# IOIO-OTG.net
KiCad netlist of a schematic drawn in EAGLE
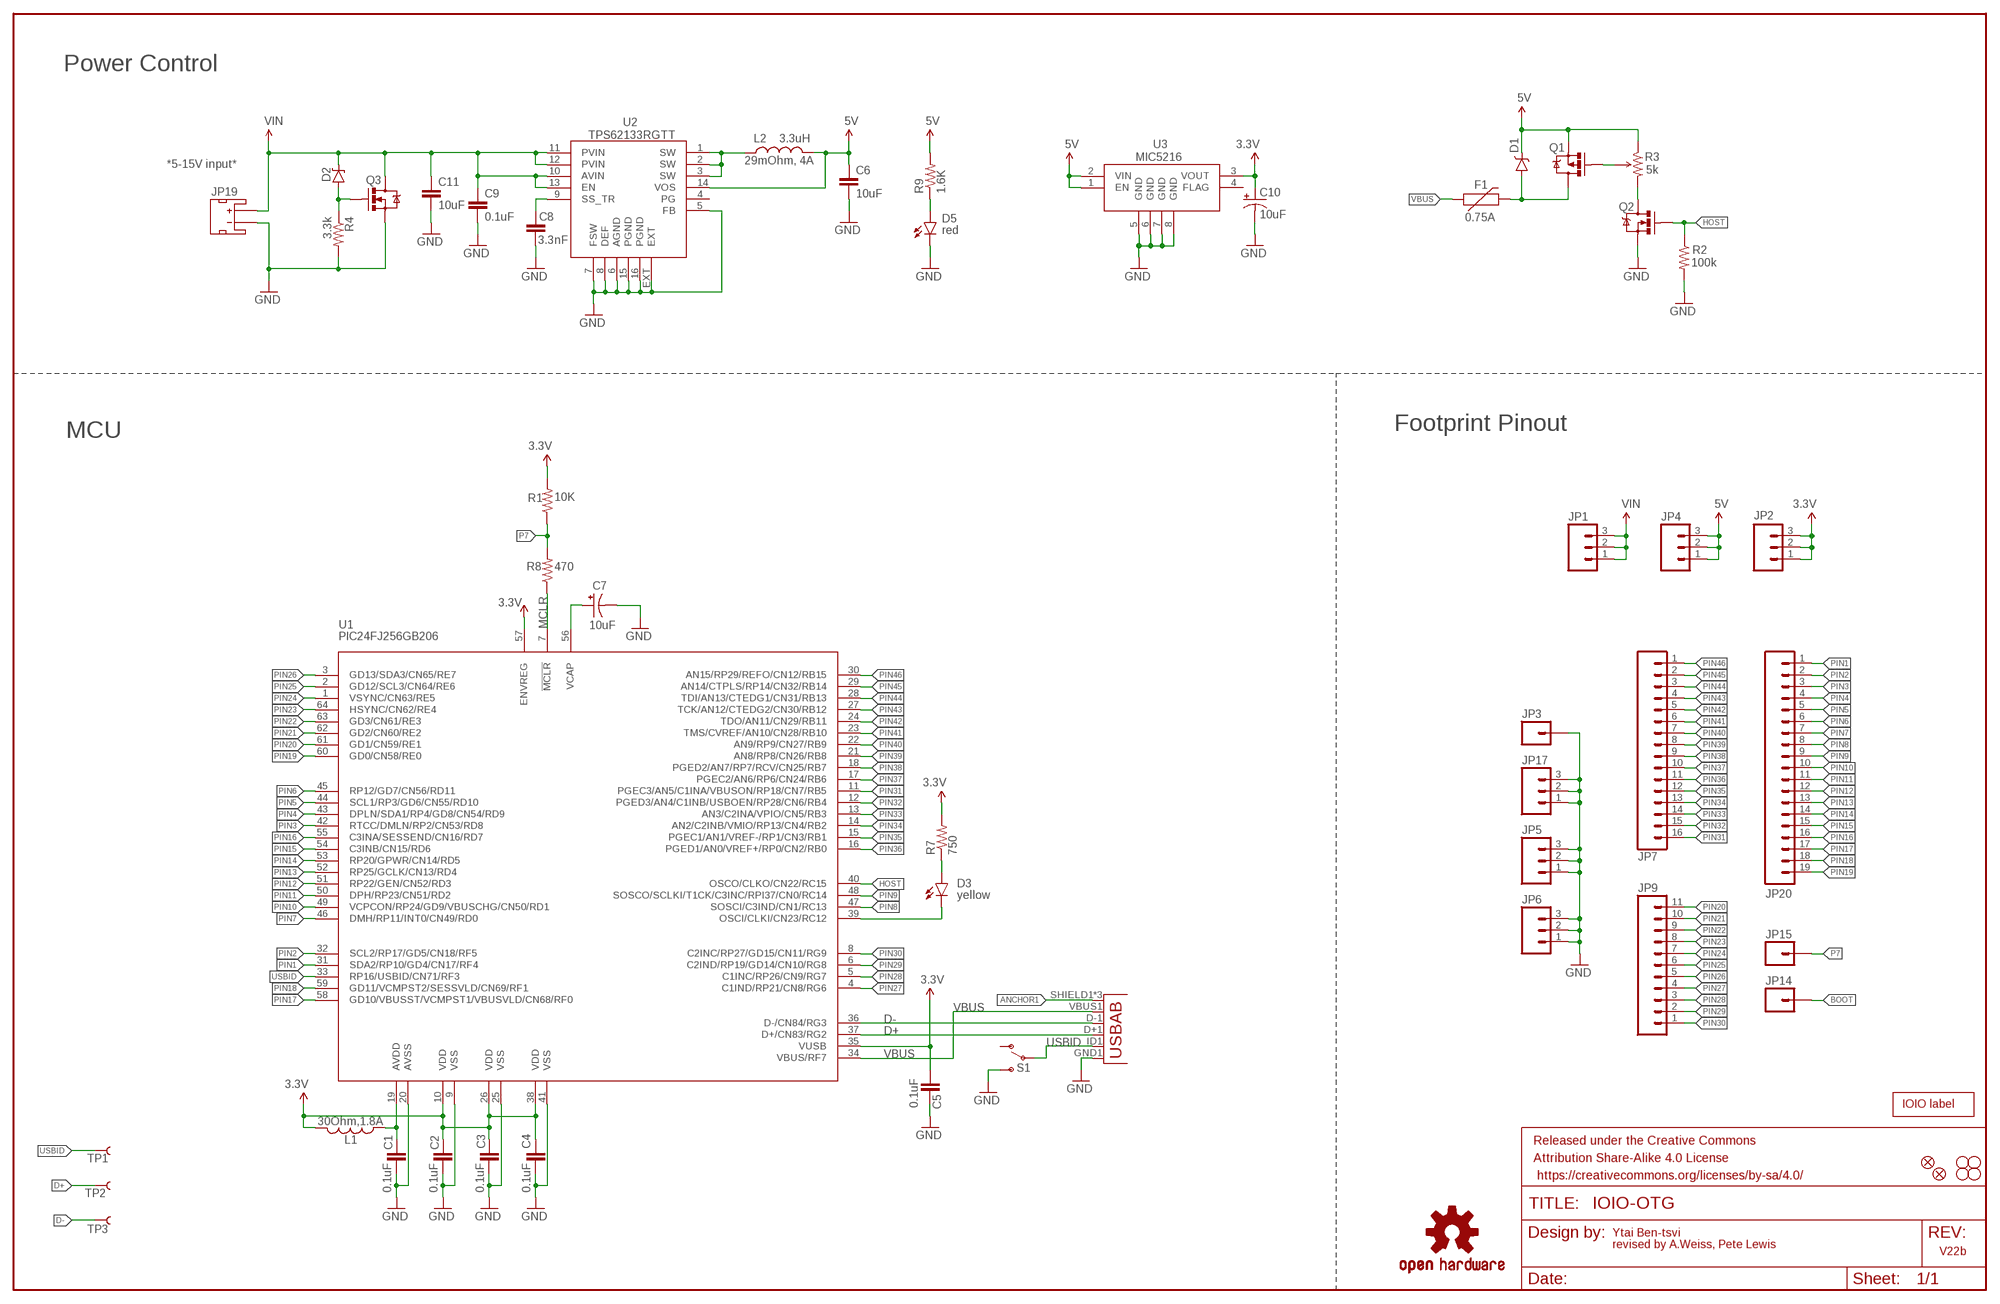
[diagram p0: schematic, sheet 1]

(export (version "E")
  (design (tool "Eeschema 10.0.6"))
  (components
    (comp (ref "C1")
      (value "0.1uF")
      (footprint "eagle-import:0603-CAP")
      (libsource (lib "eagle-import") (part "0.1UF-25V(+80/-20%)(0603)"))
    )
    (comp (ref "C2")
      (value "0.1uF")
      (footprint "eagle-import:0603-CAP")
      (libsource (lib "eagle-import") (part "0.1UF-25V(+80/-20%)(0603)"))
    )
    (comp (ref "C3")
      (value "0.1uF")
      (footprint "eagle-import:0603-CAP")
      (libsource (lib "eagle-import") (part "0.1UF-25V(+80/-20%)(0603)"))
    )
    (comp (ref "C4")
      (value "0.1uF")
      (footprint "eagle-import:0603-CAP")
      (libsource (lib "eagle-import") (part "0.1UF-25V(+80/-20%)(0603)"))
    )
    (comp (ref "C5")
      (value "0.1uF")
      (footprint "eagle-import:0603-CAP")
      (libsource (lib "eagle-import") (part "0.1UF-25V(+80/-20%)(0603)"))
    )
    (comp (ref "C6")
      (value "10uF")
      (footprint "eagle-import:0805-CAP")
      (fields (field (name "PART#") "LMK212BJ106KG-T"))
      (libsource (lib "eagle-import") (part "10UF10V10%(0805)"))
    )
    (comp (ref "C7")
      (value "10uF")
      (footprint "eagle-import:EIA3216")
      (libsource (lib "eagle-import") (part "10UF-16V-10%(TANT)"))
    )
    (comp (ref "C8")
      (value "3.3nF")
      (footprint "eagle-import:0603-CAP")
      (libsource (lib "eagle-import") (part "3.3NF-100V-10%(0603)"))
    )
    (comp (ref "C9")
      (value "0.1uF")
      (footprint "eagle-import:0603-CAP")
      (libsource (lib "eagle-import") (part "0.1UF-25V(+80/-20%)(0603)"))
    )
    (comp (ref "C10")
      (value "10uF")
      (footprint "eagle-import:EIA3216")
      (fields (field (name "PART#") "TAJA106K016RNJ"))
      (libsource (lib "eagle-import") (part "10UF-16V-10%(TANT)"))
    )
    (comp (ref "C11")
      (value "10uF")
      (footprint "eagle-import:1210")
      (fields (field (name "PART#") "UMK325C7106MM-T"))
      (libsource (lib "eagle-import") (part "10UF50V20%(1210)"))
    )
    (comp (ref "D1")
      (value "B340A")
      (footprint "eagle-import:SMA-DIODE")
      (fields (field (name "PART#") "B340A"))
      (libsource (lib "eagle-import") (part "DIODE-SCHOTTKY-B340A"))
    )
    (comp (ref "D2")
      (value "DZ2J160M0L")
      (footprint "eagle-import:PANASONIC_SMINI2-F5-B")
      (fields (field (name "PART#") "DZ2J150M0L"))
      (libsource (lib "eagle-import") (part "DIODE-ZENERDZ2J150M0L"))
    )
    (comp (ref "D3")
      (value "Yellow")
      (footprint "eagle-import:LED-0603")
      (libsource (lib "eagle-import") (part "LED-YELLOW0603-SMART"))
    )
    (comp (ref "D5")
      (value "Red")
      (footprint "eagle-import:LED-0603")
      (libsource (lib "eagle-import") (part "LED-RED0603-SMART"))
    )
    (comp (ref "F1")
      (value "0.75A")
      (footprint "eagle-import:PTC-1206")
      (fields (field (name "PART#") "0ZCA0075FF2G"))
      (libsource (lib "eagle-import") (part "PTCSMD"))
    )
    (comp (ref "FRAME2")
      (value "FRAME-LEDGER")
      (footprint "eagle-import:CREATIVE_COMMONS")
      (libsource (lib "eagle-import") (part "FRAME-LEDGER"))
    )
    (comp (ref "JP1")
      (value "M03PTH")
      (footprint "eagle-import:1X03")
      (libsource (lib "eagle-import") (part "M03PTH"))
    )
    (comp (ref "JP2")
      (value "M03PTH")
      (footprint "eagle-import:1X03")
      (libsource (lib "eagle-import") (part "M03PTH"))
    )
    (comp (ref "JP3")
      (value "M01PTH")
      (footprint "eagle-import:1X01")
      (libsource (lib "eagle-import") (part "M01PTH"))
    )
    (comp (ref "JP4")
      (value "M03PTH")
      (footprint "eagle-import:1X03")
      (libsource (lib "eagle-import") (part "M03PTH"))
    )
    (comp (ref "JP5")
      (value "M03PTH")
      (footprint "eagle-import:1X03")
      (libsource (lib "eagle-import") (part "M03PTH"))
    )
    (comp (ref "JP6")
      (value "M03PTH")
      (footprint "eagle-import:1X03")
      (libsource (lib "eagle-import") (part "M03PTH"))
    )
    (comp (ref "JP7")
      (value "M161X16_NO_SILK")
      (footprint "eagle-import:1X16_NO_SILK")
      (libsource (lib "eagle-import") (part "M161X16_NO_SILK"))
    )
    (comp (ref "JP8")
      (value "FIDUCIALUFIDUCIAL")
      (footprint "eagle-import:MICRO-FIDUCIAL")
      (libsource (lib "eagle-import") (part "FIDUCIALUFIDUCIAL"))
    )
    (comp (ref "JP9")
      (value "M111X11_NO_SILK")
      (footprint "eagle-import:1X11_NO_SILK")
      (libsource (lib "eagle-import") (part "M111X11_NO_SILK"))
    )
    (comp (ref "JP10")
      (value "STAND-OFF")
      (footprint "eagle-import:STAND-OFF")
      (libsource (lib "eagle-import") (part "STAND-OFF"))
    )
    (comp (ref "JP11")
      (value "STAND-OFF")
      (footprint "eagle-import:STAND-OFF")
      (libsource (lib "eagle-import") (part "STAND-OFF"))
    )
    (comp (ref "JP12")
      (value "STAND-OFF")
      (footprint "eagle-import:STAND-OFF")
      (libsource (lib "eagle-import") (part "STAND-OFF"))
    )
    (comp (ref "JP13")
      (value "STAND-OFF")
      (footprint "eagle-import:STAND-OFF")
      (libsource (lib "eagle-import") (part "STAND-OFF"))
    )
    (comp (ref "JP14")
      (value "M01PTH")
      (footprint "eagle-import:1X01")
      (libsource (lib "eagle-import") (part "M01PTH"))
    )
    (comp (ref "JP15")
      (value "M01PTH")
      (footprint "eagle-import:1X01")
      (libsource (lib "eagle-import") (part "M01PTH"))
    )
    (comp (ref "JP16")
      (value "FIDUCIALUFIDUCIAL")
      (footprint "eagle-import:MICRO-FIDUCIAL")
      (libsource (lib "eagle-import") (part "FIDUCIALUFIDUCIAL"))
    )
    (comp (ref "JP17")
      (value "M03PTH")
      (footprint "eagle-import:1X03")
      (libsource (lib "eagle-import") (part "M03PTH"))
    )
    (comp (ref "JP19")
      (value "JST")
      (footprint "eagle-import:JST-2-SMD")
      (libsource (lib "eagle-import") (part "JST_2MM_MALE"))
    )
    (comp (ref "JP20")
      (value "M191X19_NO_SILK")
      (footprint "eagle-import:1X19_NO_SILK")
      (libsource (lib "eagle-import") (part "M191X19_NO_SILK"))
    )
    (comp (ref "JP21")
      (value "AB MICRO USB")
      (footprint "eagle-import:USB-AB-MICRO-SMD_V03")
      (libsource (lib "eagle-import") (part "USB-ABCONN-11794"))
    )
    (comp (ref "L1")
      (value "30Ohm,1.8A")
      (footprint "eagle-import:0603")
      (libsource (lib "eagle-import") (part "INDUCTOR30OHM,1.8A"))
    )
    (comp (ref "L2")
      (value "VLC5045T-3R3N")
      (footprint "eagle-import:CR54")
      (fields (field (name "AM") "3.3uH"))
      (libsource (lib "eagle-import") (part "INDUCTORCR54-3.3UH"))
    )
    (comp (ref "LOGO1")
      (value "OSHW-LOGOS")
      (footprint "eagle-import:OSHW-LOGO-S")
      (libsource (lib "eagle-import") (part "OSHW-LOGOS"))
    )
    (comp (ref "Q1")
      (value "IRLML2244")
      (footprint "eagle-import:SOT23-3")
      (libsource (lib "eagle-import") (part "MOSFET-PCHANNELIRLML2244"))
    )
    (comp (ref "Q2")
      (value "2N7002PW")
      (footprint "eagle-import:SOT323")
      (fields (field (name "PART#") "2N7002PW"))
      (libsource (lib "eagle-import") (part "MOSFET-NCHANNEL2N7002PW"))
    )
    (comp (ref "Q3")
      (value "MOSFET-NCHANNELAO3404A")
      (footprint "eagle-import:SOT23-3")
      (fields (field (name "PART#") "AO3404A"))
      (libsource (lib "eagle-import") (part "MOSFET-NCHANNELAO3404A"))
    )
    (comp (ref "R1")
      (value "10K")
      (footprint "eagle-import:0603-RES")
      (libsource (lib "eagle-import") (part "10KOHM-1/10W-1%(0603)0603"))
    )
    (comp (ref "R2")
      (value "100k")
      (footprint "eagle-import:0603-RES")
      (libsource (lib "eagle-import") (part "100KOHM-1/10W-1%(0603)"))
    )
    (comp (ref "R3")
      (value "TS53YL502MR10")
      (footprint "eagle-import:TRIMPOT_5MM")
      (fields (field (name "PART#") "TS53YL502MR10"))
      (libsource (lib "eagle-import") (part "TRIMPOTRES-11156"))
    )
    (comp (ref "R4")
      (value "3.3k")
      (footprint "eagle-import:0603-RES")
      (libsource (lib "eagle-import") (part "3.3KOHM1/10W1%(0603)"))
    )
    (comp (ref "R7")
      (value "750")
      (footprint "eagle-import:0603-RES")
      (libsource (lib "eagle-import") (part "750OHM1/10W1%(0603)0603"))
    )
    (comp (ref "R8")
      (value "470")
      (footprint "eagle-import:0603-RES")
      (libsource (lib "eagle-import") (part "470OHM1/10W1%(0603)"))
    )
    (comp (ref "R9")
      (value "1.6K")
      (footprint "eagle-import:0603-RES")
      (libsource (lib "eagle-import") (part "1.6KOHM-1/10W-1%(0603)0603"))
    )
    (comp (ref "S1")
      (value "SWITCH_SPDT")
      (footprint "eagle-import:KPS-1290")
      (libsource (lib "eagle-import") (part "SWITCH_SPDT"))
    )
    (comp (ref "TP1")
      (value "TEST-POINT3")
      (footprint "eagle-import:PAD.03X.03")
      (libsource (lib "eagle-import") (part "TEST-POINT3"))
    )
    (comp (ref "TP2")
      (value "TEST-POINT3")
      (footprint "eagle-import:PAD.03X.03")
      (libsource (lib "eagle-import") (part "TEST-POINT3"))
    )
    (comp (ref "TP3")
      (value "TEST-POINT3")
      (footprint "eagle-import:PAD.03X.03")
      (libsource (lib "eagle-import") (part "TEST-POINT3"))
    )
    (comp (ref "U$6")
      (value "IOIO-OTG")
      (footprint "eagle-import:IOIO-OTG-COPPER-EXPOSED")
      (libsource (lib "eagle-import") (part "IOIO-OTG"))
    )
    (comp (ref "U1")
      (value "PIC24FJ256GB206")
      (footprint "eagle-import:PIC24FXXX_TQFP64")
      (libsource (lib "eagle-import") (part "PIC24FXXXGPX06"))
    )
    (comp (ref "U2")
      (value "TPS62133RGTT")
      (footprint "eagle-import:QFN16-3X3MM_1_1_V03")
      (libsource (lib "eagle-import") (part "TPS62133RGTT{dblquote}{dblquote}"))
    )
    (comp (ref "U3")
      (value "MIC5216")
      (footprint "eagle-import:MSOP8")
      (libsource (lib "eagle-import") (part "V_REG_MIC5216"))
    )
  )
  (nets
    (net (code "1") (name "/MCLR") (class "Default")
      (node (ref "R8") (pin "1") (pinfunction "1_1") (pintype "passive"))
      (node (ref "U1") (pin "7") (pinfunction "~{MCLR}_7") (pintype "input"))
    )
    (net (code "2") (name "3.3V") (class "Default")
      (node (ref "C10") (pin "A") (pinfunction "+_A") (pintype "passive"))
      (node (ref "C2") (pin "1") (pinfunction "1_1") (pintype "passive"))
      (node (ref "C3") (pin "1") (pinfunction "1_1") (pintype "passive"))
      (node (ref "C4") (pin "1") (pinfunction "1_1") (pintype "passive"))
      (node (ref "C5") (pin "1") (pinfunction "1_1") (pintype "passive"))
      (node (ref "JP2") (pin "1") (pinfunction "1_1") (pintype "passive"))
      (node (ref "JP2") (pin "2") (pinfunction "2_2") (pintype "passive"))
      (node (ref "JP2") (pin "3") (pinfunction "3_3") (pintype "passive"))
      (node (ref "L1") (pin "2") (pinfunction "2_2") (pintype "passive"))
      (node (ref "R1") (pin "2") (pinfunction "2_2") (pintype "passive"))
      (node (ref "R7") (pin "2") (pinfunction "2_2") (pintype "passive"))
      (node (ref "U1") (pin "10") (pinfunction "VDD_10") (pintype "power_in"))
      (node (ref "U1") (pin "26") (pinfunction "VDD_26") (pintype "power_in"))
      (node (ref "U1") (pin "35") (pinfunction "VUSB_35") (pintype "power_in"))
      (node (ref "U1") (pin "38") (pinfunction "VDD_38") (pintype "power_in"))
      (node (ref "U1") (pin "57") (pinfunction "ENVREG_57") (pintype "input"))
      (node (ref "U3") (pin "3") (pinfunction "VOUT_3") (pintype "bidirectional"))
    )
    (net (code "3") (name "5V") (class "Default")
      (node (ref "C6") (pin "1") (pinfunction "1_1") (pintype "passive"))
      (node (ref "D1") (pin "C") (pinfunction "C_C") (pintype "passive"))
      (node (ref "JP4") (pin "1") (pinfunction "1_1") (pintype "passive"))
      (node (ref "JP4") (pin "2") (pinfunction "2_2") (pintype "passive"))
      (node (ref "JP4") (pin "3") (pinfunction "3_3") (pintype "passive"))
      (node (ref "L2") (pin "P$2") (pinfunction "2_P$2") (pintype "passive"))
      (node (ref "Q1") (pin "2") (pinfunction "S_2") (pintype "passive"))
      (node (ref "R3") (pin "A") (pinfunction "CCW_A") (pintype "passive"))
      (node (ref "R9") (pin "2") (pinfunction "2_2") (pintype "passive"))
      (node (ref "U2") (pin "14") (pinfunction "VOS_14") (pintype "bidirectional"))
      (node (ref "U3") (pin "1") (pinfunction "EN_1") (pintype "bidirectional"))
      (node (ref "U3") (pin "2") (pinfunction "VIN_2") (pintype "bidirectional"))
    )
    (net (code "4") (name "ANCHOR1") (class "Default")
      (node (ref "JP21") (pin "SHIELD1") (pinfunction "SHIELD_SHIELD1") (pintype "bidirectional"))
      (node (ref "JP21") (pin "SHIELD2") (pinfunction "SHIELD_SHIELD2") (pintype "bidirectional"))
      (node (ref "JP21") (pin "SHIELD3") (pinfunction "SHIELD_SHIELD3") (pintype "bidirectional"))
    )
    (net (code "5") (name "BOOT") (class "Default")
      (node (ref "D3") (pin "C") (pinfunction "C_C") (pintype "passive"))
      (node (ref "JP14") (pin "1") (pinfunction "1_1") (pintype "passive"))
      (node (ref "U1") (pin "39") (pinfunction "OSCI/CLKI/CN23/RC12_39") (pintype "bidirectional"))
    )
    (net (code "6") (name "D+") (class "Default")
      (node (ref "JP21") (pin "D+1") (pinfunction "D+_D+1") (pintype "bidirectional"))
      (node (ref "TP2") (pin "P$1") (pinfunction "1_P$1") (pintype "bidirectional"))
      (node (ref "U1") (pin "37") (pinfunction "D+/CN83/RG2_37") (pintype "bidirectional"))
    )
    (net (code "7") (name "D-") (class "Default")
      (node (ref "JP21") (pin "D-1") (pinfunction "D-_D-1") (pintype "bidirectional"))
      (node (ref "TP3") (pin "P$1") (pinfunction "1_P$1") (pintype "bidirectional"))
      (node (ref "U1") (pin "36") (pinfunction "D-/CN84/RG3_36") (pintype "bidirectional"))
    )
    (net (code "8") (name "GND") (class "Default")
      (node (ref "C1") (pin "2") (pinfunction "2_2") (pintype "passive"))
      (node (ref "C10") (pin "C") (pinfunction "-_C") (pintype "passive"))
      (node (ref "C11") (pin "2") (pinfunction "2_2") (pintype "passive"))
      (node (ref "C2") (pin "2") (pinfunction "2_2") (pintype "passive"))
      (node (ref "C3") (pin "2") (pinfunction "2_2") (pintype "passive"))
      (node (ref "C4") (pin "2") (pinfunction "2_2") (pintype "passive"))
      (node (ref "C5") (pin "2") (pinfunction "2_2") (pintype "passive"))
      (node (ref "C6") (pin "2") (pinfunction "2_2") (pintype "passive"))
      (node (ref "C7") (pin "C") (pinfunction "-_C") (pintype "passive"))
      (node (ref "C8") (pin "2") (pinfunction "2_2") (pintype "passive"))
      (node (ref "C9") (pin "2") (pinfunction "2_2") (pintype "passive"))
      (node (ref "D5") (pin "C") (pinfunction "C_C") (pintype "passive"))
      (node (ref "JP17") (pin "1") (pinfunction "1_1") (pintype "passive"))
      (node (ref "JP17") (pin "2") (pinfunction "2_2") (pintype "passive"))
      (node (ref "JP17") (pin "3") (pinfunction "3_3") (pintype "passive"))
      (node (ref "JP19") (pin "1") (pinfunction "-_1") (pintype "bidirectional"))
      (node (ref "JP21") (pin "GND1") (pinfunction "GND_GND1") (pintype "bidirectional"))
      (node (ref "JP3") (pin "1") (pinfunction "1_1") (pintype "passive"))
      (node (ref "JP5") (pin "1") (pinfunction "1_1") (pintype "passive"))
      (node (ref "JP5") (pin "2") (pinfunction "2_2") (pintype "passive"))
      (node (ref "JP5") (pin "3") (pinfunction "3_3") (pintype "passive"))
      (node (ref "JP6") (pin "1") (pinfunction "1_1") (pintype "passive"))
      (node (ref "JP6") (pin "2") (pinfunction "2_2") (pintype "passive"))
      (node (ref "JP6") (pin "3") (pinfunction "3_3") (pintype "passive"))
      (node (ref "Q2") (pin "2") (pinfunction "S_2") (pintype "passive"))
      (node (ref "Q3") (pin "2") (pinfunction "S_2") (pintype "passive"))
      (node (ref "R2") (pin "2") (pinfunction "2_2") (pintype "passive"))
      (node (ref "R4") (pin "2") (pinfunction "2_2") (pintype "passive"))
      (node (ref "S1") (pin "S") (pinfunction "S_S") (pintype "passive"))
      (node (ref "U1") (pin "20") (pinfunction "AVSS_20") (pintype "power_in"))
      (node (ref "U1") (pin "25") (pinfunction "VSS_25") (pintype "power_in"))
      (node (ref "U1") (pin "41") (pinfunction "VSS_41") (pintype "power_in"))
      (node (ref "U1") (pin "9") (pinfunction "VSS_9") (pintype "power_in"))
      (node (ref "U2") (pin "15") (pinfunction "PGND_15") (pintype "bidirectional"))
      (node (ref "U2") (pin "16") (pinfunction "PGND_16") (pintype "bidirectional"))
      (node (ref "U2") (pin "5") (pinfunction "FB_5") (pintype "bidirectional"))
      (node (ref "U2") (pin "6") (pinfunction "AGND_6") (pintype "bidirectional"))
      (node (ref "U2") (pin "7") (pinfunction "FSW_7") (pintype "bidirectional"))
      (node (ref "U2") (pin "8") (pinfunction "DEF_8") (pintype "bidirectional"))
      (node (ref "U2") (pin "EXT") (pinfunction "EXT_EXT") (pintype "bidirectional"))
      (node (ref "U3") (pin "5") (pinfunction "GND_5") (pintype "bidirectional"))
      (node (ref "U3") (pin "6") (pinfunction "GND_6") (pintype "bidirectional"))
      (node (ref "U3") (pin "7") (pinfunction "GND_7") (pintype "bidirectional"))
      (node (ref "U3") (pin "8") (pinfunction "GND_8") (pintype "bidirectional"))
    )
    (net (code "9") (name "HOST") (class "Default")
      (node (ref "Q2") (pin "1") (pinfunction "G_1") (pintype "passive"))
      (node (ref "R2") (pin "1") (pinfunction "1_1") (pintype "passive"))
      (node (ref "U1") (pin "40") (pinfunction "OSCO/CLKO/CN22/RC15_40") (pintype "bidirectional"))
    )
    (net (code "10") (name "Net-(C7-+)") (class "Default")
      (node (ref "C7") (pin "A") (pinfunction "+_A") (pintype "passive"))
      (node (ref "U1") (pin "56") (pinfunction "VCAP_56") (pintype "power_in"))
    )
    (net (code "11") (name "Net-(D3-PadA)") (class "Default")
      (node (ref "D3") (pin "A") (pinfunction "A_A") (pintype "passive"))
      (node (ref "R7") (pin "1") (pinfunction "1_1") (pintype "passive"))
    )
    (net (code "12") (name "Net-(D5-PadA)") (class "Default")
      (node (ref "D5") (pin "A") (pinfunction "A_A") (pintype "passive"))
      (node (ref "R9") (pin "1") (pinfunction "1_1") (pintype "passive"))
    )
    (net (code "13") (name "Net-(L2-1)") (class "Default")
      (node (ref "L2") (pin "P$1") (pinfunction "1_P$1") (pintype "passive"))
      (node (ref "U2") (pin "1") (pinfunction "SW_1") (pintype "bidirectional"))
      (node (ref "U2") (pin "2") (pinfunction "SW_2") (pintype "bidirectional"))
      (node (ref "U2") (pin "3") (pinfunction "SW_3") (pintype "bidirectional"))
    )
    (net (code "14") (name "Net-(Q1-D)") (class "Default")
      (node (ref "D1") (pin "A") (pinfunction "A_A") (pintype "passive"))
      (node (ref "F1") (pin "2") (pinfunction "2_2") (pintype "bidirectional"))
      (node (ref "Q1") (pin "3") (pinfunction "D_3") (pintype "passive"))
    )
    (net (code "15") (name "Net-(Q1-G)") (class "Default")
      (node (ref "Q1") (pin "1") (pinfunction "G_1") (pintype "passive"))
      (node (ref "R3") (pin "B") (pinfunction "WIPER_B") (pintype "passive"))
    )
    (net (code "16") (name "Net-(Q2-D)") (class "Default")
      (node (ref "Q2") (pin "3") (pinfunction "D_3") (pintype "passive"))
      (node (ref "R3") (pin "C") (pinfunction "CW_C") (pintype "passive"))
    )
    (net (code "17") (name "Net-(Q3-G)") (class "Default")
      (node (ref "D2") (pin "A") (pinfunction "A_A") (pintype "passive"))
      (node (ref "Q3") (pin "1") (pinfunction "G_1") (pintype "passive"))
      (node (ref "R4") (pin "1") (pinfunction "1_1") (pintype "passive"))
    )
    (net (code "18") (name "Net-(U1-AVDD)") (class "Default")
      (node (ref "C1") (pin "1") (pinfunction "1_1") (pintype "passive"))
      (node (ref "L1") (pin "1") (pinfunction "1_1") (pintype "passive"))
      (node (ref "U1") (pin "19") (pinfunction "AVDD_19") (pintype "power_in"))
    )
    (net (code "19") (name "Net-(U2-SS_TR)") (class "Default")
      (node (ref "C8") (pin "1") (pinfunction "1_1") (pintype "passive"))
      (node (ref "U2") (pin "9") (pinfunction "SS_TR_9") (pintype "bidirectional"))
    )
    (net (code "20") (name "P7") (class "Default")
      (node (ref "JP15") (pin "1") (pinfunction "1_1") (pintype "passive"))
      (node (ref "R1") (pin "1") (pinfunction "1_1") (pintype "passive"))
      (node (ref "R8") (pin "2") (pinfunction "2_2") (pintype "passive"))
    )
    (net (code "21") (name "PIN1") (class "Default")
      (node (ref "JP20") (pin "1") (pinfunction "1_1") (pintype "passive"))
      (node (ref "U1") (pin "31") (pinfunction "SDA2/RP10/GD4/CN17/RF4_31") (pintype "bidirectional"))
    )
    (net (code "22") (name "PIN2") (class "Default")
      (node (ref "JP20") (pin "2") (pinfunction "2_2") (pintype "passive"))
      (node (ref "U1") (pin "32") (pinfunction "SCL2/RP17/GD5/CN18/RF5_32") (pintype "bidirectional"))
    )
    (net (code "23") (name "PIN3") (class "Default")
      (node (ref "JP20") (pin "3") (pinfunction "3_3") (pintype "passive"))
      (node (ref "U1") (pin "42") (pinfunction "RTCC/DMLN/RP2/CN53/RD8_42") (pintype "bidirectional"))
    )
    (net (code "24") (name "PIN4") (class "Default")
      (node (ref "JP20") (pin "4") (pinfunction "4_4") (pintype "passive"))
      (node (ref "U1") (pin "43") (pinfunction "DPLN/SDA1/RP4/GD8/CN54/RD9_43") (pintype "bidirectional"))
    )
    (net (code "25") (name "PIN5") (class "Default")
      (node (ref "JP20") (pin "5") (pinfunction "5_5") (pintype "passive"))
      (node (ref "U1") (pin "44") (pinfunction "SCL1/RP3/GD6/CN55/RD10_44") (pintype "bidirectional"))
    )
    (net (code "26") (name "PIN6") (class "Default")
      (node (ref "JP20") (pin "6") (pinfunction "6_6") (pintype "passive"))
      (node (ref "U1") (pin "45") (pinfunction "RP12/GD7/CN56/RD11_45") (pintype "bidirectional"))
    )
    (net (code "27") (name "PIN7") (class "Default")
      (node (ref "JP20") (pin "7") (pinfunction "7_7") (pintype "passive"))
      (node (ref "U1") (pin "46") (pinfunction "DMH/RP11/INT0/CN49/RD0_46") (pintype "bidirectional"))
    )
    (net (code "28") (name "PIN8") (class "Default")
      (node (ref "JP20") (pin "8") (pinfunction "8_8") (pintype "passive"))
      (node (ref "U1") (pin "47") (pinfunction "SOSCI/C3IND/CN1/RC13_47") (pintype "bidirectional"))
    )
    (net (code "29") (name "PIN9") (class "Default")
      (node (ref "JP20") (pin "9") (pinfunction "9_9") (pintype "passive"))
      (node (ref "U1") (pin "48") (pinfunction "SOSCO/SCLKI/T1CK/C3INC/RPI37/CN0/RC14_48") (pintype "bidirectional"))
    )
    (net (code "30") (name "PIN10") (class "Default")
      (node (ref "JP20") (pin "10") (pinfunction "10_10") (pintype "passive"))
      (node (ref "U1") (pin "49") (pinfunction "VCPCON/RP24/GD9/VBUSCHG/CN50/RD1_49") (pintype "bidirectional"))
    )
    (net (code "31") (name "PIN11") (class "Default")
      (node (ref "JP20") (pin "11") (pinfunction "11_11") (pintype "passive"))
      (node (ref "U1") (pin "50") (pinfunction "DPH/RP23/CN51/RD2_50") (pintype "bidirectional"))
    )
    (net (code "32") (name "PIN12") (class "Default")
      (node (ref "JP20") (pin "12") (pinfunction "12_12") (pintype "passive"))
      (node (ref "U1") (pin "51") (pinfunction "RP22/GEN/CN52/RD3_51") (pintype "bidirectional"))
    )
    (net (code "33") (name "PIN13") (class "Default")
      (node (ref "JP20") (pin "13") (pinfunction "13_13") (pintype "passive"))
      (node (ref "U1") (pin "52") (pinfunction "RP25/GCLK/CN13/RD4_52") (pintype "bidirectional"))
    )
    (net (code "34") (name "PIN14") (class "Default")
      (node (ref "JP20") (pin "14") (pinfunction "14_14") (pintype "passive"))
      (node (ref "U1") (pin "53") (pinfunction "RP20/GPWR/CN14/RD5_53") (pintype "bidirectional"))
    )
    (net (code "35") (name "PIN15") (class "Default")
      (node (ref "JP20") (pin "15") (pinfunction "15_15") (pintype "passive"))
      (node (ref "U1") (pin "54") (pinfunction "C3INB/CN15/RD6_54") (pintype "bidirectional"))
    )
    (net (code "36") (name "PIN16") (class "Default")
      (node (ref "JP20") (pin "16") (pinfunction "16_16") (pintype "passive"))
      (node (ref "U1") (pin "55") (pinfunction "C3INA/SESSEND/CN16/RD7_55") (pintype "bidirectional"))
    )
    (net (code "37") (name "PIN17") (class "Default")
      (node (ref "JP20") (pin "17") (pinfunction "17_17") (pintype "passive"))
      (node (ref "U1") (pin "58") (pinfunction "GD10/VBUSST/VCMPST1/VBUSVLD/CN68/RF0_58") (pintype "bidirectional"))
    )
    (net (code "38") (name "PIN18") (class "Default")
      (node (ref "JP20") (pin "18") (pinfunction "18_18") (pintype "passive"))
      (node (ref "U1") (pin "59") (pinfunction "GD11/VCMPST2/SESSVLD/CN69/RF1_59") (pintype "bidirectional"))
    )
    (net (code "39") (name "PIN19") (class "Default")
      (node (ref "JP20") (pin "19") (pinfunction "19_19") (pintype "passive"))
      (node (ref "U1") (pin "60") (pinfunction "GD0/CN58/RE0_60") (pintype "bidirectional"))
    )
    (net (code "40") (name "PIN20") (class "Default")
      (node (ref "JP9") (pin "11") (pinfunction "11_11") (pintype "passive"))
      (node (ref "U1") (pin "61") (pinfunction "GD1/CN59/RE1_61") (pintype "bidirectional"))
    )
    (net (code "41") (name "PIN21") (class "Default")
      (node (ref "JP9") (pin "10") (pinfunction "10_10") (pintype "passive"))
      (node (ref "U1") (pin "62") (pinfunction "GD2/CN60/RE2_62") (pintype "bidirectional"))
    )
    (net (code "42") (name "PIN22") (class "Default")
      (node (ref "JP9") (pin "9") (pinfunction "9_9") (pintype "passive"))
      (node (ref "U1") (pin "63") (pinfunction "GD3/CN61/RE3_63") (pintype "bidirectional"))
    )
    (net (code "43") (name "PIN23") (class "Default")
      (node (ref "JP9") (pin "8") (pinfunction "8_8") (pintype "passive"))
      (node (ref "U1") (pin "64") (pinfunction "HSYNC/CN62/RE4_64") (pintype "bidirectional"))
    )
    (net (code "44") (name "PIN24") (class "Default")
      (node (ref "JP9") (pin "7") (pinfunction "7_7") (pintype "passive"))
      (node (ref "U1") (pin "1") (pinfunction "VSYNC/CN63/RE5_1") (pintype "bidirectional"))
    )
    (net (code "45") (name "PIN25") (class "Default")
      (node (ref "JP9") (pin "6") (pinfunction "6_6") (pintype "passive"))
      (node (ref "U1") (pin "2") (pinfunction "GD12/SCL3/CN64/RE6_2") (pintype "bidirectional"))
    )
    (net (code "46") (name "PIN26") (class "Default")
      (node (ref "JP9") (pin "5") (pinfunction "5_5") (pintype "passive"))
      (node (ref "U1") (pin "3") (pinfunction "GD13/SDA3/CN65/RE7_3") (pintype "bidirectional"))
    )
    (net (code "47") (name "PIN27") (class "Default")
      (node (ref "JP9") (pin "4") (pinfunction "4_4") (pintype "passive"))
      (node (ref "U1") (pin "4") (pinfunction "C1IND/RP21/CN8/RG6_4") (pintype "bidirectional"))
    )
    (net (code "48") (name "PIN28") (class "Default")
      (node (ref "JP9") (pin "3") (pinfunction "3_3") (pintype "passive"))
      (node (ref "U1") (pin "5") (pinfunction "C1INC/RP26/CN9/RG7_5") (pintype "bidirectional"))
    )
    (net (code "49") (name "PIN29") (class "Default")
      (node (ref "JP9") (pin "2") (pinfunction "2_2") (pintype "passive"))
      (node (ref "U1") (pin "6") (pinfunction "C2IND/RP19/GD14/CN10/RG8_6") (pintype "bidirectional"))
    )
    (net (code "50") (name "PIN30") (class "Default")
      (node (ref "JP9") (pin "1") (pinfunction "1_1") (pintype "passive"))
      (node (ref "U1") (pin "8") (pinfunction "C2INC/RP27/GD15/CN11/RG9_8") (pintype "bidirectional"))
    )
    (net (code "51") (name "PIN31") (class "Default")
      (node (ref "JP7") (pin "16") (pinfunction "16_16") (pintype "passive"))
      (node (ref "U1") (pin "11") (pinfunction "PGEC3/AN5/C1INA/VBUSON/RP18/CN7/RB5_11") (pintype "bidirectional"))
    )
    (net (code "52") (name "PIN32") (class "Default")
      (node (ref "JP7") (pin "15") (pinfunction "15_15") (pintype "passive"))
      (node (ref "U1") (pin "12") (pinfunction "PGED3/AN4/C1INB/USBOEN/RP28/CN6/RB4_12") (pintype "bidirectional"))
    )
    (net (code "53") (name "PIN33") (class "Default")
      (node (ref "JP7") (pin "14") (pinfunction "14_14") (pintype "passive"))
      (node (ref "U1") (pin "13") (pinfunction "AN3/C2INA/VPIO/CN5/RB3_13") (pintype "bidirectional"))
    )
    (net (code "54") (name "PIN34") (class "Default")
      (node (ref "JP7") (pin "13") (pinfunction "13_13") (pintype "passive"))
      (node (ref "U1") (pin "14") (pinfunction "AN2/C2INB/VMIO/RP13/CN4/RB2_14") (pintype "bidirectional"))
    )
    (net (code "55") (name "PIN35") (class "Default")
      (node (ref "JP7") (pin "12") (pinfunction "12_12") (pintype "passive"))
      (node (ref "U1") (pin "15") (pinfunction "PGEC1/AN1/VREF-/RP1/CN3/RB1_15") (pintype "bidirectional"))
    )
    (net (code "56") (name "PIN36") (class "Default")
      (node (ref "JP7") (pin "11") (pinfunction "11_11") (pintype "passive"))
      (node (ref "U1") (pin "16") (pinfunction "PGED1/AN0/VREF+/RP0/CN2/RB0_16") (pintype "bidirectional"))
    )
    (net (code "57") (name "PIN37") (class "Default")
      (node (ref "JP7") (pin "10") (pinfunction "10_10") (pintype "passive"))
      (node (ref "U1") (pin "17") (pinfunction "PGEC2/AN6/RP6/CN24/RB6_17") (pintype "bidirectional"))
    )
    (net (code "58") (name "PIN38") (class "Default")
      (node (ref "JP7") (pin "9") (pinfunction "9_9") (pintype "passive"))
      (node (ref "U1") (pin "18") (pinfunction "PGED2/AN7/RP7/RCV/CN25/RB7_18") (pintype "bidirectional"))
    )
    (net (code "59") (name "PIN39") (class "Default")
      (node (ref "JP7") (pin "8") (pinfunction "8_8") (pintype "passive"))
      (node (ref "U1") (pin "21") (pinfunction "AN8/RP8/CN26/RB8_21") (pintype "bidirectional"))
    )
    (net (code "60") (name "PIN40") (class "Default")
      (node (ref "JP7") (pin "7") (pinfunction "7_7") (pintype "passive"))
      (node (ref "U1") (pin "22") (pinfunction "AN9/RP9/CN27/RB9_22") (pintype "bidirectional"))
    )
    (net (code "61") (name "PIN41") (class "Default")
      (node (ref "JP7") (pin "6") (pinfunction "6_6") (pintype "passive"))
      (node (ref "U1") (pin "23") (pinfunction "TMS/CVREF/AN10/CN28/RB10_23") (pintype "bidirectional"))
    )
    (net (code "62") (name "PIN42") (class "Default")
      (node (ref "JP7") (pin "5") (pinfunction "5_5") (pintype "passive"))
      (node (ref "U1") (pin "24") (pinfunction "TDO/AN11/CN29/RB11_24") (pintype "bidirectional"))
    )
    (net (code "63") (name "PIN43") (class "Default")
      (node (ref "JP7") (pin "4") (pinfunction "4_4") (pintype "passive"))
      (node (ref "U1") (pin "27") (pinfunction "TCK/AN12/CTEDG2/CN30/RB12_27") (pintype "bidirectional"))
    )
    (net (code "64") (name "PIN44") (class "Default")
      (node (ref "JP7") (pin "3") (pinfunction "3_3") (pintype "passive"))
      (node (ref "U1") (pin "28") (pinfunction "TDI/AN13/CTEDG1/CN31/RB13_28") (pintype "bidirectional"))
    )
    (net (code "65") (name "PIN45") (class "Default")
      (node (ref "JP7") (pin "2") (pinfunction "2_2") (pintype "passive"))
      (node (ref "U1") (pin "29") (pinfunction "AN14/CTPLS/RP14/CN32/RB14_29") (pintype "bidirectional"))
    )
    (net (code "66") (name "PIN46") (class "Default")
      (node (ref "JP7") (pin "1") (pinfunction "1_1") (pintype "passive"))
      (node (ref "U1") (pin "30") (pinfunction "AN15/RP29/REFO/CN12/RB15_30") (pintype "bidirectional"))
    )
    (net (code "67") (name "USBID") (class "Default")
      (node (ref "JP21") (pin "ID1") (pinfunction "USBID_ID1") (pintype "bidirectional"))
      (node (ref "S1") (pin "P") (pinfunction "P_P") (pintype "passive"))
      (node (ref "TP1") (pin "P$1") (pinfunction "1_P$1") (pintype "bidirectional"))
      (node (ref "U1") (pin "33") (pinfunction "RP16/USBID/CN71/RF3_33") (pintype "bidirectional"))
    )
    (net (code "68") (name "VBUS") (class "Default")
      (node (ref "F1") (pin "1") (pinfunction "1_1") (pintype "bidirectional"))
      (node (ref "JP21") (pin "VBUS1") (pinfunction "VBUS_VBUS1") (pintype "bidirectional"))
      (node (ref "U1") (pin "34") (pinfunction "VBUS/RF7_34") (pintype "input"))
    )
    (net (code "69") (name "VIN") (class "Default")
      (node (ref "C11") (pin "1") (pinfunction "1_1") (pintype "passive"))
      (node (ref "C9") (pin "1") (pinfunction "1_1") (pintype "passive"))
      (node (ref "D2") (pin "C") (pinfunction "C_C") (pintype "passive"))
      (node (ref "JP1") (pin "1") (pinfunction "1_1") (pintype "passive"))
      (node (ref "JP1") (pin "2") (pinfunction "2_2") (pintype "passive"))
      (node (ref "JP1") (pin "3") (pinfunction "3_3") (pintype "passive"))
      (node (ref "JP19") (pin "2") (pinfunction "+_2") (pintype "bidirectional"))
      (node (ref "Q3") (pin "3") (pinfunction "D_3") (pintype "passive"))
      (node (ref "U2") (pin "10") (pinfunction "AVIN_10") (pintype "bidirectional"))
      (node (ref "U2") (pin "11") (pinfunction "PVIN_11") (pintype "bidirectional"))
      (node (ref "U2") (pin "12") (pinfunction "PVIN_12") (pintype "bidirectional"))
      (node (ref "U2") (pin "13") (pinfunction "EN_13") (pintype "bidirectional"))
    )
    (net (code "70") (name "unconnected-(JP19-PAD1-PadNC1)") (class "Default")
      (node (ref "JP19") (pin "NC1") (pinfunction "PAD1_NC1") (pintype "bidirectional"))
    )
    (net (code "71") (name "unconnected-(JP19-PAD2-PadNC2)") (class "Default")
      (node (ref "JP19") (pin "NC2") (pinfunction "PAD2_NC2") (pintype "bidirectional"))
    )
    (net (code "72") (name "unconnected-(S1-PadO)") (class "Default")
      (node (ref "S1") (pin "O") (pinfunction "O_O") (pintype "passive"))
    )
    (net (code "73") (name "unconnected-(U2-PG-Pad4)") (class "Default")
      (node (ref "U2") (pin "4") (pinfunction "PG_4") (pintype "bidirectional"))
    )
    (net (code "74") (name "unconnected-(U3-FLAG-Pad4)") (class "Default")
      (node (ref "U3") (pin "4") (pinfunction "FLAG_4") (pintype "bidirectional"))
    )
  )
)
